# YOTSUBA__X_EM_ver_3_2.net
KiCad netlist of a schematic drawn in EAGLE
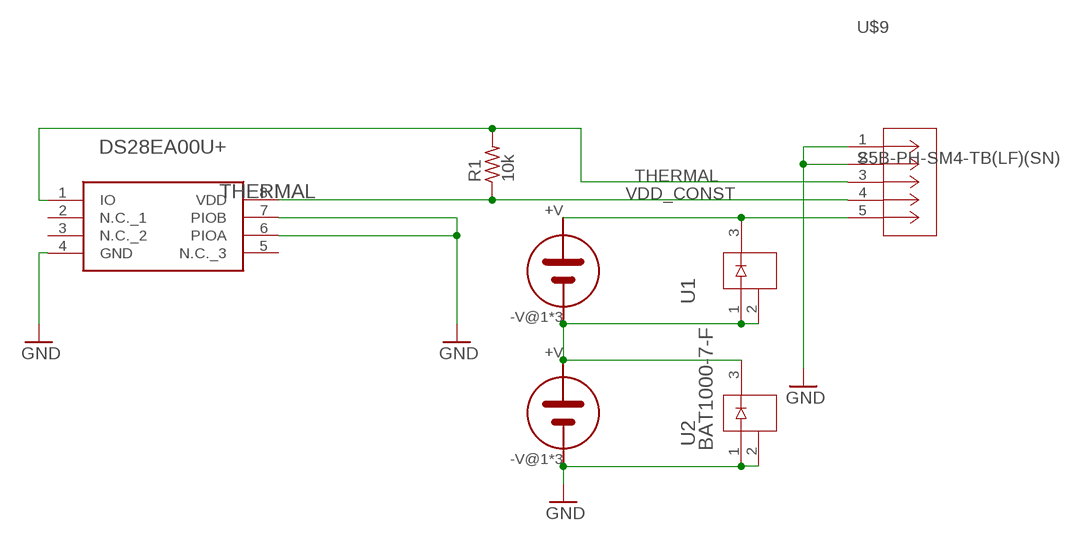
[diagram p0: schematic, sheet 1]

(export (version "E")
  (design (tool "Eeschema 10.0.6"))
  (components
    (comp (ref "R1")
      (value "10k")
      (footprint "eagle-import:R0805")
      (libsource (lib "eagle-import") (part "R-US_R0805"))
    )
    (comp (ref "THERMAL")
      (value "DS28EA00U+")
      (footprint "eagle-import:SOP65P490X110-8N")
      (fields (field (name "MOUSER_PART_NUMBER") "700-DS28EA00U"))
      (libsource (lib "eagle-import") (part "DS28EA00U+"))
    )
    (comp (ref "U$2")
      (value "3G30A")
      (footprint "eagle-import:SOLAR_3G30A")
      (libsource (lib "eagle-import") (part "3G30A"))
    )
    (comp (ref "U$3")
      (value "3G30A")
      (footprint "eagle-import:SOLAR_3G30A")
      (libsource (lib "eagle-import") (part "3G30A"))
    )
    (comp (ref "U$9")
      (value "S5B-PH-SM4-TB(LF)(SN)")
      (footprint "eagle-import:CONN_S5B-PH-SM4-TB_JST")
      (fields (field (name "COPYRIGHT") "Copyright (C) 2023 Ultra Librarian. All rights reserved."))
      (libsource (lib "eagle-import") (part "S5B-PH-SM4-TB(LF)(SN)"))
    )
    (comp (ref "U1")
      (value "BAT1000-7-F")
      (footprint "eagle-import:SOT23_BAT_DIO")
      (fields (field (name "COPYRIGHT") "Copyright (C) 2023 Ultra Librarian. All rights reserved."))
      (libsource (lib "eagle-import") (part "BAT1000-7-F"))
    )
    (comp (ref "U2")
      (value "BAT1000-7-F")
      (footprint "eagle-import:SOT23_BAT_DIO")
      (fields (field (name "COPYRIGHT") "Copyright (C) 2023 Ultra Librarian. All rights reserved."))
      (libsource (lib "eagle-import") (part "BAT1000-7-F"))
    )
  )
  (nets
    (net (code "1") (name "/THERMAL") (class "Default")
      (node (ref "R1") (pin "2") (pinfunction "2_2") (pintype "passive"))
      (node (ref "THERMAL") (pin "1") (pinfunction "IO_1") (pintype "bidirectional"))
      (node (ref "U$9") (pin "3") (pinfunction "3_3") (pintype "passive"))
    )
    (net (code "2") (name "/VDD_CONST") (class "Default")
      (node (ref "R1") (pin "1") (pinfunction "1_1") (pintype "passive"))
      (node (ref "THERMAL") (pin "8") (pinfunction "VDD_8") (pintype "bidirectional"))
      (node (ref "U$9") (pin "4") (pinfunction "4_4") (pintype "passive"))
    )
    (net (code "3") (name "GND") (class "Default")
      (node (ref "THERMAL") (pin "4") (pinfunction "GND_4") (pintype "bidirectional"))
      (node (ref "THERMAL") (pin "6") (pinfunction "PIOA_6") (pintype "bidirectional"))
      (node (ref "THERMAL") (pin "7") (pinfunction "PIOB_7") (pintype "bidirectional"))
      (node (ref "U$3") (pin "-V@1") (pinfunction "-V_-V@1") (pintype "bidirectional"))
      (node (ref "U$3") (pin "-V@2") (pinfunction "-V_-V@2") (pintype "bidirectional"))
      (node (ref "U$3") (pin "-V@3") (pinfunction "-V_-V@3") (pintype "bidirectional"))
      (node (ref "U$9") (pin "1") (pinfunction "1_1") (pintype "passive"))
      (node (ref "U$9") (pin "2") (pinfunction "2_2") (pintype "passive"))
      (node (ref "U2") (pin "1") (pinfunction "1_1") (pintype "passive"))
      (node (ref "U2") (pin "2") (pinfunction "2_2") (pintype "passive"))
    )
    (net (code "4") (name "Net-(U$2--V-Pad-V@1)") (class "Default")
      (node (ref "U$2") (pin "-V@1") (pinfunction "-V_-V@1") (pintype "bidirectional"))
      (node (ref "U$2") (pin "-V@2") (pinfunction "-V_-V@2") (pintype "bidirectional"))
      (node (ref "U$2") (pin "-V@3") (pinfunction "-V_-V@3") (pintype "bidirectional"))
      (node (ref "U$3") (pin "+V") (pinfunction "+V_+V") (pintype "bidirectional"))
      (node (ref "U1") (pin "1") (pinfunction "1_1") (pintype "passive"))
      (node (ref "U1") (pin "2") (pinfunction "2_2") (pintype "passive"))
      (node (ref "U2") (pin "3") (pinfunction "3_3") (pintype "passive"))
    )
    (net (code "5") (name "Net-(U$2-Pad+V)") (class "Default")
      (node (ref "U$2") (pin "+V") (pinfunction "+V_+V") (pintype "bidirectional"))
      (node (ref "U$9") (pin "5") (pinfunction "5_5") (pintype "passive"))
      (node (ref "U1") (pin "3") (pinfunction "3_3") (pintype "passive"))
    )
    (net (code "6") (name "unconnected-(THERMAL-N.C._1-Pad2)") (class "Default")
      (node (ref "THERMAL") (pin "2") (pinfunction "N.C._1_2") (pintype "bidirectional"))
    )
    (net (code "7") (name "unconnected-(THERMAL-N.C._2-Pad3)") (class "Default")
      (node (ref "THERMAL") (pin "3") (pinfunction "N.C._2_3") (pintype "bidirectional"))
    )
    (net (code "8") (name "unconnected-(THERMAL-N.C._3-Pad5)") (class "Default")
      (node (ref "THERMAL") (pin "5") (pinfunction "N.C._3_5") (pintype "bidirectional"))
    )
  )
)
